# Motor.net
KiCad netlist of a schematic drawn in Altium Designer
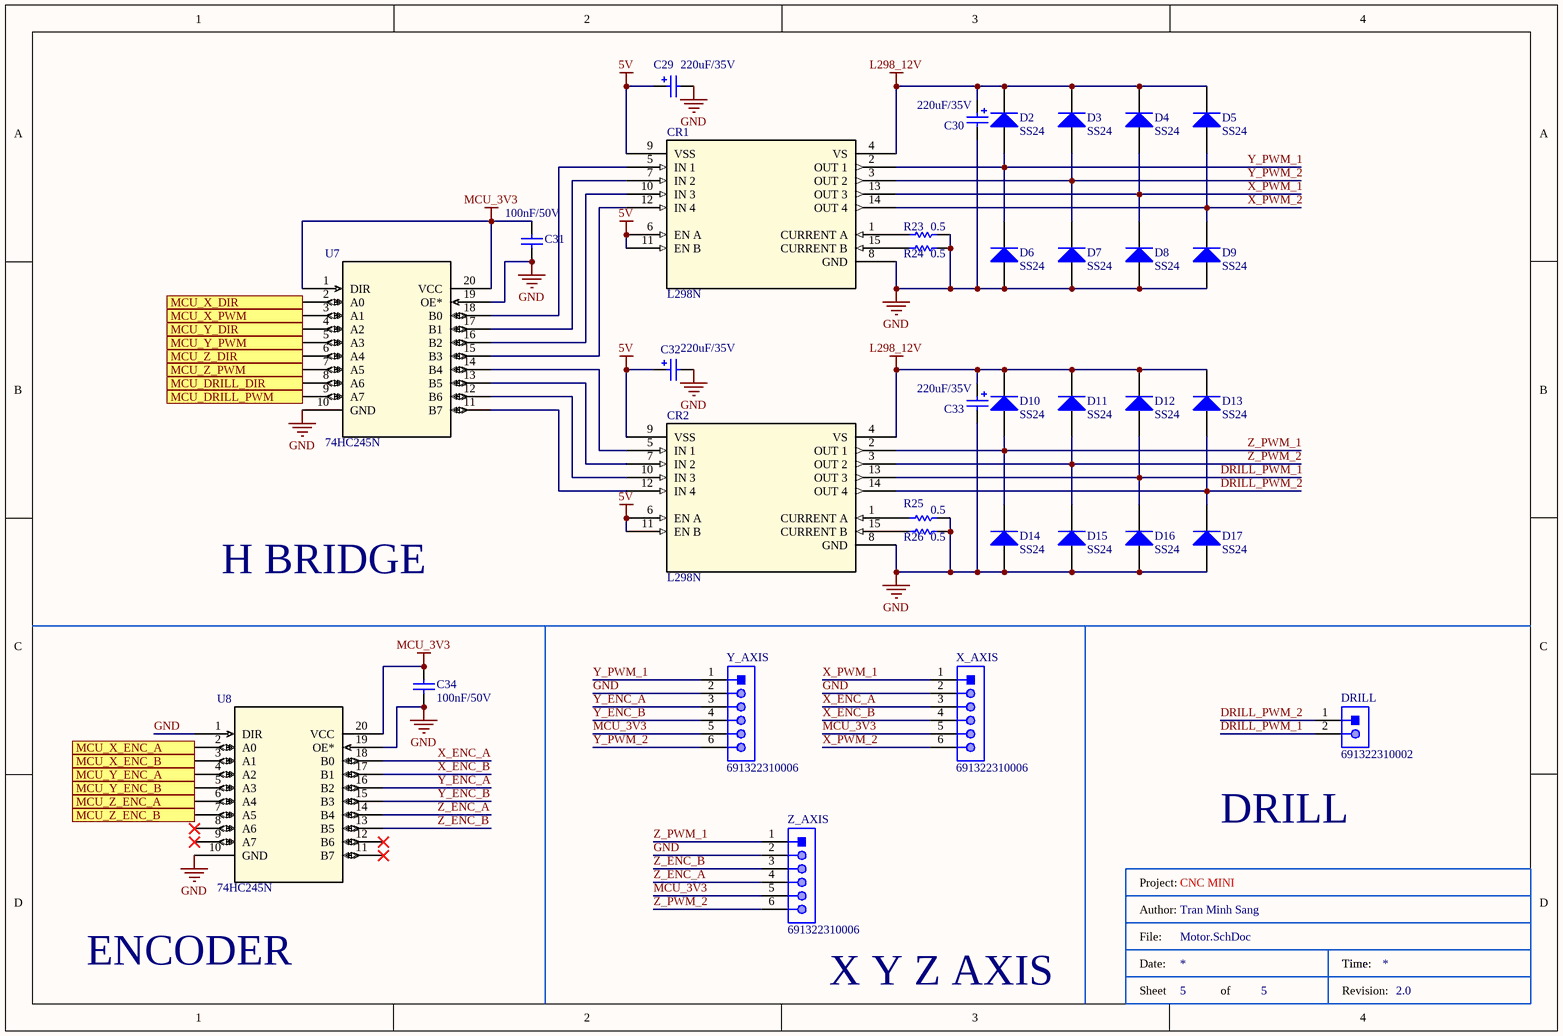
[diagram p0: Motor.SchDoc]

(export (version "E")
  (design (tool "Eeschema 10.0.6"))
  (components
    (comp (ref "C29")
      (value "220uF/35V")
      (footprint "CAP-SM-AL-SIZE-F-D8L10")
      (description "CAP ALUM 220UF 20% 35V SMD")
      (fields
        (field (name "MANUFACTURER") "Nichicon")
        (field (name "MANUFACTURER PART NUMBER") "UWT1V221MNL1GS")
      )
      (libsource (lib "capacitor-smd") (part "Cap-Al-220uF-35V-D8L10"))
    )
    (comp (ref "C30")
      (value "220uF/35V")
      (footprint "CAP-SM-AL-SIZE-F-D8L10")
      (description "CAP ALUM 220UF 20% 35V SMD")
      (fields
        (field (name "MANUFACTURER") "Nichicon")
        (field (name "MANUFACTURER PART NUMBER") "UWT1V221MNL1GS")
      )
      (libsource (lib "capacitor-smd") (part "Cap-Al-220uF-35V-D8L10"))
    )
    (comp (ref "C31")
      (value "100nF/50V")
      (footprint "CAP-SM-0805")
      (description "CAP CER 0.1UF 50V Y5V 0805")
      (fields
        (field (name "MANUFACTURER") "Samsung Electro-Mechanics")
        (field (name "MANUFACTURER PART NUMBER") "CL21F104ZBCNNNC")
      )
      (libsource (lib "capacitor-smd") (part "Cap-100nF-50V-0805"))
    )
    (comp (ref "C32")
      (value "220uF/35V")
      (footprint "CAP-SM-AL-SIZE-F-D8L10")
      (description "CAP ALUM 220UF 20% 35V SMD")
      (fields
        (field (name "MANUFACTURER") "Nichicon")
        (field (name "MANUFACTURER PART NUMBER") "UWT1V221MNL1GS")
      )
      (libsource (lib "capacitor-smd") (part "Cap-Al-220uF-35V-D8L10"))
    )
    (comp (ref "C33")
      (value "220uF/35V")
      (footprint "CAP-SM-AL-SIZE-F-D8L10")
      (description "CAP ALUM 220UF 20% 35V SMD")
      (fields
        (field (name "MANUFACTURER") "Nichicon")
        (field (name "MANUFACTURER PART NUMBER") "UWT1V221MNL1GS")
      )
      (libsource (lib "capacitor-smd") (part "Cap-Al-220uF-35V-D8L10"))
    )
    (comp (ref "C34")
      (value "100nF/50V")
      (footprint "CAP-SM-0805")
      (description "CAP CER 0.1UF 50V Y5V 0805")
      (fields
        (field (name "MANUFACTURER") "Samsung Electro-Mechanics")
        (field (name "MANUFACTURER PART NUMBER") "CL21F104ZBCNNNC")
      )
      (libsource (lib "capacitor-smd") (part "Cap-100nF-50V-0805"))
    )
    (comp (ref "CR1")
      (value "L298N")
      (footprint "Multiwatt15_V_STM")
      (description "No Description Available")
      (fields (field (name "COPYRIGHT") "Copyright (C) 2023 Ultra Librarian. All rights reserved."))
      (libsource (lib "MiniCNC_ver2") (part "L298N"))
    )
    (comp (ref "CR2")
      (value "L298N")
      (footprint "Multiwatt15_V_STM")
      (description "No Description Available")
      (fields (field (name "COPYRIGHT") "Copyright (C) 2023 Ultra Librarian. All rights reserved."))
      (libsource (lib "MiniCNC_ver2") (part "L298N"))
    )
    (comp (ref "D2")
      (value "SS24")
      (footprint "SS24")
      (description "DIODE SCHOTTKY 40V 2A DO214AA")
      (fields (field (name "MANUFACTURER") "ON Semiconductor"))
      (libsource (lib "diode-smd") (part "Diode-SS24"))
    )
    (comp (ref "D3")
      (value "SS24")
      (footprint "SS24")
      (description "DIODE SCHOTTKY 40V 2A DO214AA")
      (fields (field (name "MANUFACTURER") "ON Semiconductor"))
      (libsource (lib "diode-smd") (part "Diode-SS24"))
    )
    (comp (ref "D4")
      (value "SS24")
      (footprint "SS24")
      (description "DIODE SCHOTTKY 40V 2A DO214AA")
      (fields (field (name "MANUFACTURER") "ON Semiconductor"))
      (libsource (lib "diode-smd") (part "Diode-SS24"))
    )
    (comp (ref "D5")
      (value "SS24")
      (footprint "SS24")
      (description "DIODE SCHOTTKY 40V 2A DO214AA")
      (fields (field (name "MANUFACTURER") "ON Semiconductor"))
      (libsource (lib "diode-smd") (part "Diode-SS24"))
    )
    (comp (ref "D6")
      (value "SS24")
      (footprint "SS24")
      (description "DIODE SCHOTTKY 40V 2A DO214AA")
      (fields (field (name "MANUFACTURER") "ON Semiconductor"))
      (libsource (lib "diode-smd") (part "Diode-SS24"))
    )
    (comp (ref "D7")
      (value "SS24")
      (footprint "SS24")
      (description "DIODE SCHOTTKY 40V 2A DO214AA")
      (fields (field (name "MANUFACTURER") "ON Semiconductor"))
      (libsource (lib "diode-smd") (part "Diode-SS24"))
    )
    (comp (ref "D8")
      (value "SS24")
      (footprint "SS24")
      (description "DIODE SCHOTTKY 40V 2A DO214AA")
      (fields (field (name "MANUFACTURER") "ON Semiconductor"))
      (libsource (lib "diode-smd") (part "Diode-SS24"))
    )
    (comp (ref "D9")
      (value "SS24")
      (footprint "SS24")
      (description "DIODE SCHOTTKY 40V 2A DO214AA")
      (fields (field (name "MANUFACTURER") "ON Semiconductor"))
      (libsource (lib "diode-smd") (part "Diode-SS24"))
    )
    (comp (ref "D10")
      (value "SS24")
      (footprint "SS24")
      (description "DIODE SCHOTTKY 40V 2A DO214AA")
      (fields (field (name "MANUFACTURER") "ON Semiconductor"))
      (libsource (lib "diode-smd") (part "Diode-SS24"))
    )
    (comp (ref "D11")
      (value "SS24")
      (footprint "SS24")
      (description "DIODE SCHOTTKY 40V 2A DO214AA")
      (fields (field (name "MANUFACTURER") "ON Semiconductor"))
      (libsource (lib "diode-smd") (part "Diode-SS24"))
    )
    (comp (ref "D12")
      (value "SS24")
      (footprint "SS24")
      (description "DIODE SCHOTTKY 40V 2A DO214AA")
      (fields (field (name "MANUFACTURER") "ON Semiconductor"))
      (libsource (lib "diode-smd") (part "Diode-SS24"))
    )
    (comp (ref "D13")
      (value "SS24")
      (footprint "SS24")
      (description "DIODE SCHOTTKY 40V 2A DO214AA")
      (fields (field (name "MANUFACTURER") "ON Semiconductor"))
      (libsource (lib "diode-smd") (part "Diode-SS24"))
    )
    (comp (ref "D14")
      (value "SS24")
      (footprint "SS24")
      (description "DIODE SCHOTTKY 40V 2A DO214AA")
      (fields (field (name "MANUFACTURER") "ON Semiconductor"))
      (libsource (lib "diode-smd") (part "Diode-SS24"))
    )
    (comp (ref "D15")
      (value "SS24")
      (footprint "SS24")
      (description "DIODE SCHOTTKY 40V 2A DO214AA")
      (fields (field (name "MANUFACTURER") "ON Semiconductor"))
      (libsource (lib "diode-smd") (part "Diode-SS24"))
    )
    (comp (ref "D16")
      (value "SS24")
      (footprint "SS24")
      (description "DIODE SCHOTTKY 40V 2A DO214AA")
      (fields (field (name "MANUFACTURER") "ON Semiconductor"))
      (libsource (lib "diode-smd") (part "Diode-SS24"))
    )
    (comp (ref "D17")
      (value "SS24")
      (footprint "SS24")
      (description "DIODE SCHOTTKY 40V 2A DO214AA")
      (fields (field (name "MANUFACTURER") "ON Semiconductor"))
      (libsource (lib "diode-smd") (part "Diode-SS24"))
    )
    (comp (ref "DRILL")
      (value "691322310002")
      (footprint "691322310002")
      (description "WR-TBL Serie 322 Horizontal PCB Header, Pluggable, pitch 3.81mm, 2p")
      (fields (field (name "PUBLISHER") "Wurth Elektronik"))
      (libsource (lib "WR-TBL_Pluggable PCB Header") (part "691322310002"))
    )
    (comp (ref "R23")
      (value "0.5")
      (footprint "resistor-smd:RES-SM-0805")
      (description "RES 0 OHM JUMPER 0805")
      (fields
        (field (name "MANUFACTURER") "Vishay Dale")
        (field (name "MANUFACTURER PART NUMBER") "WSL080500000ZEA9")
      )
      (libsource (lib "resistor-smd") (part "Res-0-0805"))
    )
    (comp (ref "R24")
      (value "0.5")
      (footprint "resistor-smd:RES-SM-0805")
      (description "RES 0 OHM JUMPER 0805")
      (fields
        (field (name "MANUFACTURER") "Vishay Dale")
        (field (name "MANUFACTURER PART NUMBER") "WSL080500000ZEA9")
      )
      (libsource (lib "resistor-smd") (part "Res-0-0805"))
    )
    (comp (ref "R25")
      (value "0.5")
      (footprint "resistor-smd:RES-SM-0805")
      (description "RES 0 OHM JUMPER 0805")
      (fields
        (field (name "MANUFACTURER") "Vishay Dale")
        (field (name "MANUFACTURER PART NUMBER") "WSL080500000ZEA9")
      )
      (libsource (lib "resistor-smd") (part "Res-0-0805"))
    )
    (comp (ref "R26")
      (value "0.5")
      (footprint "resistor-smd:RES-SM-0805")
      (description "RES 0 OHM JUMPER 0805")
      (fields
        (field (name "MANUFACTURER") "Vishay Dale")
        (field (name "MANUFACTURER PART NUMBER") "WSL080500000ZEA9")
      )
      (libsource (lib "resistor-smd") (part "Res-0-0805"))
    )
    (comp (ref "U7")
      (value "74HC245N")
      (footprint "74HC245N")
      (description "No Description Available")
      (fields (field (name "COPYRIGHT") "Copyright (C) 2022 Ultra Librarian. All rights reserved."))
      (libsource (lib "CNCMicaMini") (part "74HC245N"))
    )
    (comp (ref "U8")
      (value "74HC245N")
      (footprint "74HC245N")
      (description "No Description Available")
      (fields (field (name "COPYRIGHT") "Copyright (C) 2022 Ultra Librarian. All rights reserved."))
      (libsource (lib "CNCMicaMini") (part "74HC245N"))
    )
    (comp (ref "X_AXIS")
      (value "691322310006")
      (footprint "691322310006")
      (description "WR-TBL Serie 322 Horizontal PCB Header, Pluggable, pitch 3.81mm, 6p")
      (fields (field (name "PUBLISHER") "Wurth Elektronik"))
      (libsource (lib "WR-TBL_Pluggable PCB Header") (part "691322310006"))
    )
    (comp (ref "Y_AXIS")
      (value "691322310006")
      (footprint "691322310006")
      (description "WR-TBL Serie 322 Horizontal PCB Header, Pluggable, pitch 3.81mm, 6p")
      (fields (field (name "PUBLISHER") "Wurth Elektronik"))
      (libsource (lib "WR-TBL_Pluggable PCB Header") (part "691322310006"))
    )
    (comp (ref "Z_AXIS")
      (value "691322310006")
      (footprint "691322310006")
      (description "WR-TBL Serie 322 Horizontal PCB Header, Pluggable, pitch 3.81mm, 6p")
      (fields (field (name "PUBLISHER") "Wurth Elektronik"))
      (libsource (lib "WR-TBL_Pluggable PCB Header") (part "691322310006"))
    )
  )
  (nets
    (net (code "1") (name "/DRILL_PWM_1") (class "Default")
      (node (ref "CR2") (pin "13") (pinfunction "OUT_3_13") (pintype "output"))
      (node (ref "D12") (pin "2") (pinfunction "A_2") (pintype "passive"))
      (node (ref "D16") (pin "1") (pinfunction "K_1") (pintype "passive"))
      (node (ref "DRILL") (pin "2") (pinfunction "2_2") (pintype "passive"))
    )
    (net (code "2") (name "/DRILL_PWM_2") (class "Default")
      (node (ref "CR2") (pin "14") (pinfunction "OUT_4_14") (pintype "output"))
      (node (ref "D13") (pin "2") (pinfunction "A_2") (pintype "passive"))
      (node (ref "D17") (pin "1") (pinfunction "K_1") (pintype "passive"))
      (node (ref "DRILL") (pin "1") (pinfunction "1_1") (pintype "passive"))
    )
    (net (code "3") (name "/MCU_DRILL_DIR") (class "Default")
      (node (ref "U7") (pin "8") (pinfunction "A6_8") (pintype "bidirectional"))
    )
    (net (code "4") (name "/MCU_DRILL_PWM") (class "Default")
      (node (ref "U7") (pin "9") (pinfunction "A7_9") (pintype "bidirectional"))
    )
    (net (code "5") (name "/MCU_X_DIR") (class "Default")
      (node (ref "U7") (pin "2") (pinfunction "A0_2") (pintype "bidirectional"))
    )
    (net (code "6") (name "/MCU_X_ENC_A") (class "Default")
      (node (ref "U8") (pin "2") (pinfunction "A0_2") (pintype "bidirectional"))
    )
    (net (code "7") (name "/MCU_X_ENC_B") (class "Default")
      (node (ref "U8") (pin "3") (pinfunction "A1_3") (pintype "bidirectional"))
    )
    (net (code "8") (name "/MCU_X_PWM") (class "Default")
      (node (ref "U7") (pin "3") (pinfunction "A1_3") (pintype "bidirectional"))
    )
    (net (code "9") (name "/MCU_Y_DIR") (class "Default")
      (node (ref "U7") (pin "4") (pinfunction "A2_4") (pintype "bidirectional"))
    )
    (net (code "10") (name "/MCU_Y_ENC_A") (class "Default")
      (node (ref "U8") (pin "4") (pinfunction "A2_4") (pintype "bidirectional"))
    )
    (net (code "11") (name "/MCU_Y_ENC_B") (class "Default")
      (node (ref "U8") (pin "5") (pinfunction "A3_5") (pintype "bidirectional"))
    )
    (net (code "12") (name "/MCU_Y_PWM") (class "Default")
      (node (ref "U7") (pin "5") (pinfunction "A3_5") (pintype "bidirectional"))
    )
    (net (code "13") (name "/MCU_Z_DIR") (class "Default")
      (node (ref "U7") (pin "6") (pinfunction "A4_6") (pintype "bidirectional"))
    )
    (net (code "14") (name "/MCU_Z_ENC_A") (class "Default")
      (node (ref "U8") (pin "6") (pinfunction "A4_6") (pintype "bidirectional"))
    )
    (net (code "15") (name "/MCU_Z_ENC_B") (class "Default")
      (node (ref "U8") (pin "7") (pinfunction "A5_7") (pintype "bidirectional"))
    )
    (net (code "16") (name "/MCU_Z_PWM") (class "Default")
      (node (ref "U7") (pin "7") (pinfunction "A5_7") (pintype "bidirectional"))
    )
    (net (code "17") (name "/X_ENC_A") (class "Default")
      (node (ref "U8") (pin "18") (pinfunction "B0_18") (pintype "bidirectional"))
      (node (ref "X_AXIS") (pin "3") (pinfunction "3_3") (pintype "passive"))
    )
    (net (code "18") (name "/X_ENC_B") (class "Default")
      (node (ref "U8") (pin "17") (pinfunction "B1_17") (pintype "bidirectional"))
      (node (ref "X_AXIS") (pin "4") (pinfunction "4_4") (pintype "passive"))
    )
    (net (code "19") (name "/X_PWM_1") (class "Default")
      (node (ref "CR1") (pin "13") (pinfunction "OUT_3_13") (pintype "output"))
      (node (ref "D4") (pin "2") (pinfunction "A_2") (pintype "passive"))
      (node (ref "D8") (pin "1") (pinfunction "K_1") (pintype "passive"))
      (node (ref "X_AXIS") (pin "1") (pinfunction "1_1") (pintype "passive"))
    )
    (net (code "20") (name "/X_PWM_2") (class "Default")
      (node (ref "CR1") (pin "14") (pinfunction "OUT_4_14") (pintype "output"))
      (node (ref "D5") (pin "2") (pinfunction "A_2") (pintype "passive"))
      (node (ref "D9") (pin "1") (pinfunction "K_1") (pintype "passive"))
      (node (ref "X_AXIS") (pin "6") (pinfunction "6_6") (pintype "passive"))
    )
    (net (code "21") (name "/Y_ENC_A") (class "Default")
      (node (ref "U8") (pin "16") (pinfunction "B2_16") (pintype "bidirectional"))
      (node (ref "Y_AXIS") (pin "3") (pinfunction "3_3") (pintype "passive"))
    )
    (net (code "22") (name "/Y_ENC_B") (class "Default")
      (node (ref "U8") (pin "15") (pinfunction "B3_15") (pintype "bidirectional"))
      (node (ref "Y_AXIS") (pin "4") (pinfunction "4_4") (pintype "passive"))
    )
    (net (code "23") (name "/Y_PWM_1") (class "Default")
      (node (ref "CR1") (pin "2") (pinfunction "OUT_1_2") (pintype "output"))
      (node (ref "D2") (pin "2") (pinfunction "A_2") (pintype "passive"))
      (node (ref "D6") (pin "1") (pinfunction "K_1") (pintype "passive"))
      (node (ref "Y_AXIS") (pin "1") (pinfunction "1_1") (pintype "passive"))
    )
    (net (code "24") (name "/Y_PWM_2") (class "Default")
      (node (ref "CR1") (pin "3") (pinfunction "OUT_2_3") (pintype "output"))
      (node (ref "D3") (pin "2") (pinfunction "A_2") (pintype "passive"))
      (node (ref "D7") (pin "1") (pinfunction "K_1") (pintype "passive"))
      (node (ref "Y_AXIS") (pin "6") (pinfunction "6_6") (pintype "passive"))
    )
    (net (code "25") (name "/Z_ENC_A") (class "Default")
      (node (ref "U8") (pin "14") (pinfunction "B4_14") (pintype "bidirectional"))
      (node (ref "Z_AXIS") (pin "4") (pinfunction "4_4") (pintype "passive"))
    )
    (net (code "26") (name "/Z_ENC_B") (class "Default")
      (node (ref "U8") (pin "13") (pinfunction "B5_13") (pintype "bidirectional"))
      (node (ref "Z_AXIS") (pin "3") (pinfunction "3_3") (pintype "passive"))
    )
    (net (code "27") (name "/Z_PWM_1") (class "Default")
      (node (ref "CR2") (pin "2") (pinfunction "OUT_1_2") (pintype "output"))
      (node (ref "D10") (pin "2") (pinfunction "A_2") (pintype "passive"))
      (node (ref "D14") (pin "1") (pinfunction "K_1") (pintype "passive"))
      (node (ref "Z_AXIS") (pin "1") (pinfunction "1_1") (pintype "passive"))
    )
    (net (code "28") (name "/Z_PWM_2") (class "Default")
      (node (ref "CR2") (pin "3") (pinfunction "OUT_2_3") (pintype "output"))
      (node (ref "D11") (pin "2") (pinfunction "A_2") (pintype "passive"))
      (node (ref "D15") (pin "1") (pinfunction "K_1") (pintype "passive"))
      (node (ref "Z_AXIS") (pin "6") (pinfunction "6_6") (pintype "passive"))
    )
    (net (code "29") (name "5V") (class "Default")
      (node (ref "C29") (pin "1") (pinfunction "1_1") (pintype "passive"))
      (node (ref "C32") (pin "1") (pinfunction "1_1") (pintype "passive"))
      (node (ref "CR1") (pin "11") (pinfunction "EN_B_11") (pintype "input"))
      (node (ref "CR1") (pin "6") (pinfunction "EN_A_6") (pintype "input"))
      (node (ref "CR1") (pin "9") (pinfunction "VSS_9") (pintype "power_in"))
      (node (ref "CR2") (pin "11") (pinfunction "EN_B_11") (pintype "input"))
      (node (ref "CR2") (pin "6") (pinfunction "EN_A_6") (pintype "input"))
      (node (ref "CR2") (pin "9") (pinfunction "VSS_9") (pintype "power_in"))
    )
    (net (code "30") (name "GND") (class "Default")
      (node (ref "C29") (pin "2") (pinfunction "2_2") (pintype "passive"))
      (node (ref "C30") (pin "2") (pinfunction "2_2") (pintype "passive"))
      (node (ref "C31") (pin "1") (pinfunction "1_1") (pintype "passive"))
      (node (ref "C32") (pin "2") (pinfunction "2_2") (pintype "passive"))
      (node (ref "C33") (pin "2") (pinfunction "2_2") (pintype "passive"))
      (node (ref "C34") (pin "1") (pinfunction "1_1") (pintype "passive"))
      (node (ref "CR1") (pin "8") (pinfunction "GND_8") (pintype "passive"))
      (node (ref "CR2") (pin "8") (pinfunction "GND_8") (pintype "passive"))
      (node (ref "D14") (pin "2") (pinfunction "A_2") (pintype "passive"))
      (node (ref "D15") (pin "2") (pinfunction "A_2") (pintype "passive"))
      (node (ref "D16") (pin "2") (pinfunction "A_2") (pintype "passive"))
      (node (ref "D17") (pin "2") (pinfunction "A_2") (pintype "passive"))
      (node (ref "D6") (pin "2") (pinfunction "A_2") (pintype "passive"))
      (node (ref "D7") (pin "2") (pinfunction "A_2") (pintype "passive"))
      (node (ref "D8") (pin "2") (pinfunction "A_2") (pintype "passive"))
      (node (ref "D9") (pin "2") (pinfunction "A_2") (pintype "passive"))
      (node (ref "R23") (pin "1") (pinfunction "1_1") (pintype "passive"))
      (node (ref "R24") (pin "1") (pinfunction "1_1") (pintype "passive"))
      (node (ref "R25") (pin "1") (pinfunction "1_1") (pintype "passive"))
      (node (ref "R26") (pin "1") (pinfunction "1_1") (pintype "passive"))
      (node (ref "U7") (pin "10") (pinfunction "GND_10") (pintype "power_in"))
      (node (ref "U7") (pin "19") (pinfunction "OE*_19") (pintype "input"))
      (node (ref "U8") (pin "1") (pinfunction "DIR_1") (pintype "input"))
      (node (ref "U8") (pin "10") (pinfunction "GND_10") (pintype "power_in"))
      (node (ref "U8") (pin "19") (pinfunction "OE*_19") (pintype "input"))
      (node (ref "X_AXIS") (pin "2") (pinfunction "2_2") (pintype "passive"))
      (node (ref "Y_AXIS") (pin "2") (pinfunction "2_2") (pintype "passive"))
      (node (ref "Z_AXIS") (pin "2") (pinfunction "2_2") (pintype "passive"))
    )
    (net (code "31") (name "L298_12V") (class "Default")
      (node (ref "C30") (pin "1") (pinfunction "1_1") (pintype "passive"))
      (node (ref "C33") (pin "1") (pinfunction "1_1") (pintype "passive"))
      (node (ref "CR1") (pin "4") (pinfunction "VS_4") (pintype "power_in"))
      (node (ref "CR2") (pin "4") (pinfunction "VS_4") (pintype "power_in"))
      (node (ref "D10") (pin "1") (pinfunction "K_1") (pintype "passive"))
      (node (ref "D11") (pin "1") (pinfunction "K_1") (pintype "passive"))
      (node (ref "D12") (pin "1") (pinfunction "K_1") (pintype "passive"))
      (node (ref "D13") (pin "1") (pinfunction "K_1") (pintype "passive"))
      (node (ref "D2") (pin "1") (pinfunction "K_1") (pintype "passive"))
      (node (ref "D3") (pin "1") (pinfunction "K_1") (pintype "passive"))
      (node (ref "D4") (pin "1") (pinfunction "K_1") (pintype "passive"))
      (node (ref "D5") (pin "1") (pinfunction "K_1") (pintype "passive"))
    )
    (net (code "32") (name "MCU_3V3") (class "Default")
      (node (ref "C31") (pin "2") (pinfunction "2_2") (pintype "passive"))
      (node (ref "C34") (pin "2") (pinfunction "2_2") (pintype "passive"))
      (node (ref "U7") (pin "1") (pinfunction "DIR_1") (pintype "input"))
      (node (ref "U7") (pin "20") (pinfunction "VCC_20") (pintype "power_in"))
      (node (ref "U8") (pin "20") (pinfunction "VCC_20") (pintype "power_in"))
      (node (ref "X_AXIS") (pin "5") (pinfunction "5_5") (pintype "passive"))
      (node (ref "Y_AXIS") (pin "5") (pinfunction "5_5") (pintype "passive"))
      (node (ref "Z_AXIS") (pin "5") (pinfunction "5_5") (pintype "passive"))
    )
    (net (code "33") (name "Net-(CR1-CURRENT_A)") (class "Default")
      (node (ref "CR1") (pin "1") (pinfunction "CURRENT_A_1") (pintype "input"))
      (node (ref "R23") (pin "2") (pinfunction "2_2") (pintype "passive"))
    )
    (net (code "34") (name "Net-(CR1-CURRENT_B)") (class "Default")
      (node (ref "CR1") (pin "15") (pinfunction "CURRENT_B_15") (pintype "input"))
      (node (ref "R24") (pin "2") (pinfunction "2_2") (pintype "passive"))
    )
    (net (code "35") (name "Net-(CR1-IN_1)") (class "Default")
      (node (ref "CR1") (pin "5") (pinfunction "IN_1_5") (pintype "input"))
      (node (ref "U7") (pin "18") (pinfunction "B0_18") (pintype "bidirectional"))
    )
    (net (code "36") (name "Net-(CR1-IN_2)") (class "Default")
      (node (ref "CR1") (pin "7") (pinfunction "IN_2_7") (pintype "input"))
      (node (ref "U7") (pin "17") (pinfunction "B1_17") (pintype "bidirectional"))
    )
    (net (code "37") (name "Net-(CR1-IN_3)") (class "Default")
      (node (ref "CR1") (pin "10") (pinfunction "IN_3_10") (pintype "input"))
      (node (ref "U7") (pin "16") (pinfunction "B2_16") (pintype "bidirectional"))
    )
    (net (code "38") (name "Net-(CR1-IN_4)") (class "Default")
      (node (ref "CR1") (pin "12") (pinfunction "IN_4_12") (pintype "input"))
      (node (ref "U7") (pin "15") (pinfunction "B3_15") (pintype "bidirectional"))
    )
    (net (code "39") (name "Net-(CR2-CURRENT_A)") (class "Default")
      (node (ref "CR2") (pin "1") (pinfunction "CURRENT_A_1") (pintype "input"))
      (node (ref "R25") (pin "2") (pinfunction "2_2") (pintype "passive"))
    )
    (net (code "40") (name "Net-(CR2-CURRENT_B)") (class "Default")
      (node (ref "CR2") (pin "15") (pinfunction "CURRENT_B_15") (pintype "input"))
      (node (ref "R26") (pin "2") (pinfunction "2_2") (pintype "passive"))
    )
    (net (code "41") (name "Net-(CR2-IN_1)") (class "Default")
      (node (ref "CR2") (pin "5") (pinfunction "IN_1_5") (pintype "input"))
      (node (ref "U7") (pin "14") (pinfunction "B4_14") (pintype "bidirectional"))
    )
    (net (code "42") (name "Net-(CR2-IN_2)") (class "Default")
      (node (ref "CR2") (pin "7") (pinfunction "IN_2_7") (pintype "input"))
      (node (ref "U7") (pin "13") (pinfunction "B5_13") (pintype "bidirectional"))
    )
    (net (code "43") (name "Net-(CR2-IN_3)") (class "Default")
      (node (ref "CR2") (pin "10") (pinfunction "IN_3_10") (pintype "input"))
      (node (ref "U7") (pin "12") (pinfunction "B6_12") (pintype "bidirectional"))
    )
    (net (code "44") (name "Net-(CR2-IN_4)") (class "Default")
      (node (ref "CR2") (pin "12") (pinfunction "IN_4_12") (pintype "input"))
      (node (ref "U7") (pin "11") (pinfunction "B7_11") (pintype "bidirectional"))
    )
    (net (code "45") (name "unconnected-(U8-A6-Pad8)") (class "Default")
      (node (ref "U8") (pin "8") (pinfunction "A6_8") (pintype "bidirectional+no_connect"))
    )
    (net (code "46") (name "unconnected-(U8-A7-Pad9)") (class "Default")
      (node (ref "U8") (pin "9") (pinfunction "A7_9") (pintype "bidirectional+no_connect"))
    )
    (net (code "47") (name "unconnected-(U8-B6-Pad12)") (class "Default")
      (node (ref "U8") (pin "12") (pinfunction "B6_12") (pintype "bidirectional+no_connect"))
    )
    (net (code "48") (name "unconnected-(U8-B7-Pad11)") (class "Default")
      (node (ref "U8") (pin "11") (pinfunction "B7_11") (pintype "bidirectional+no_connect"))
    )
  )
)
